# MCU.net
KiCad netlist of a schematic drawn in Altium Designer
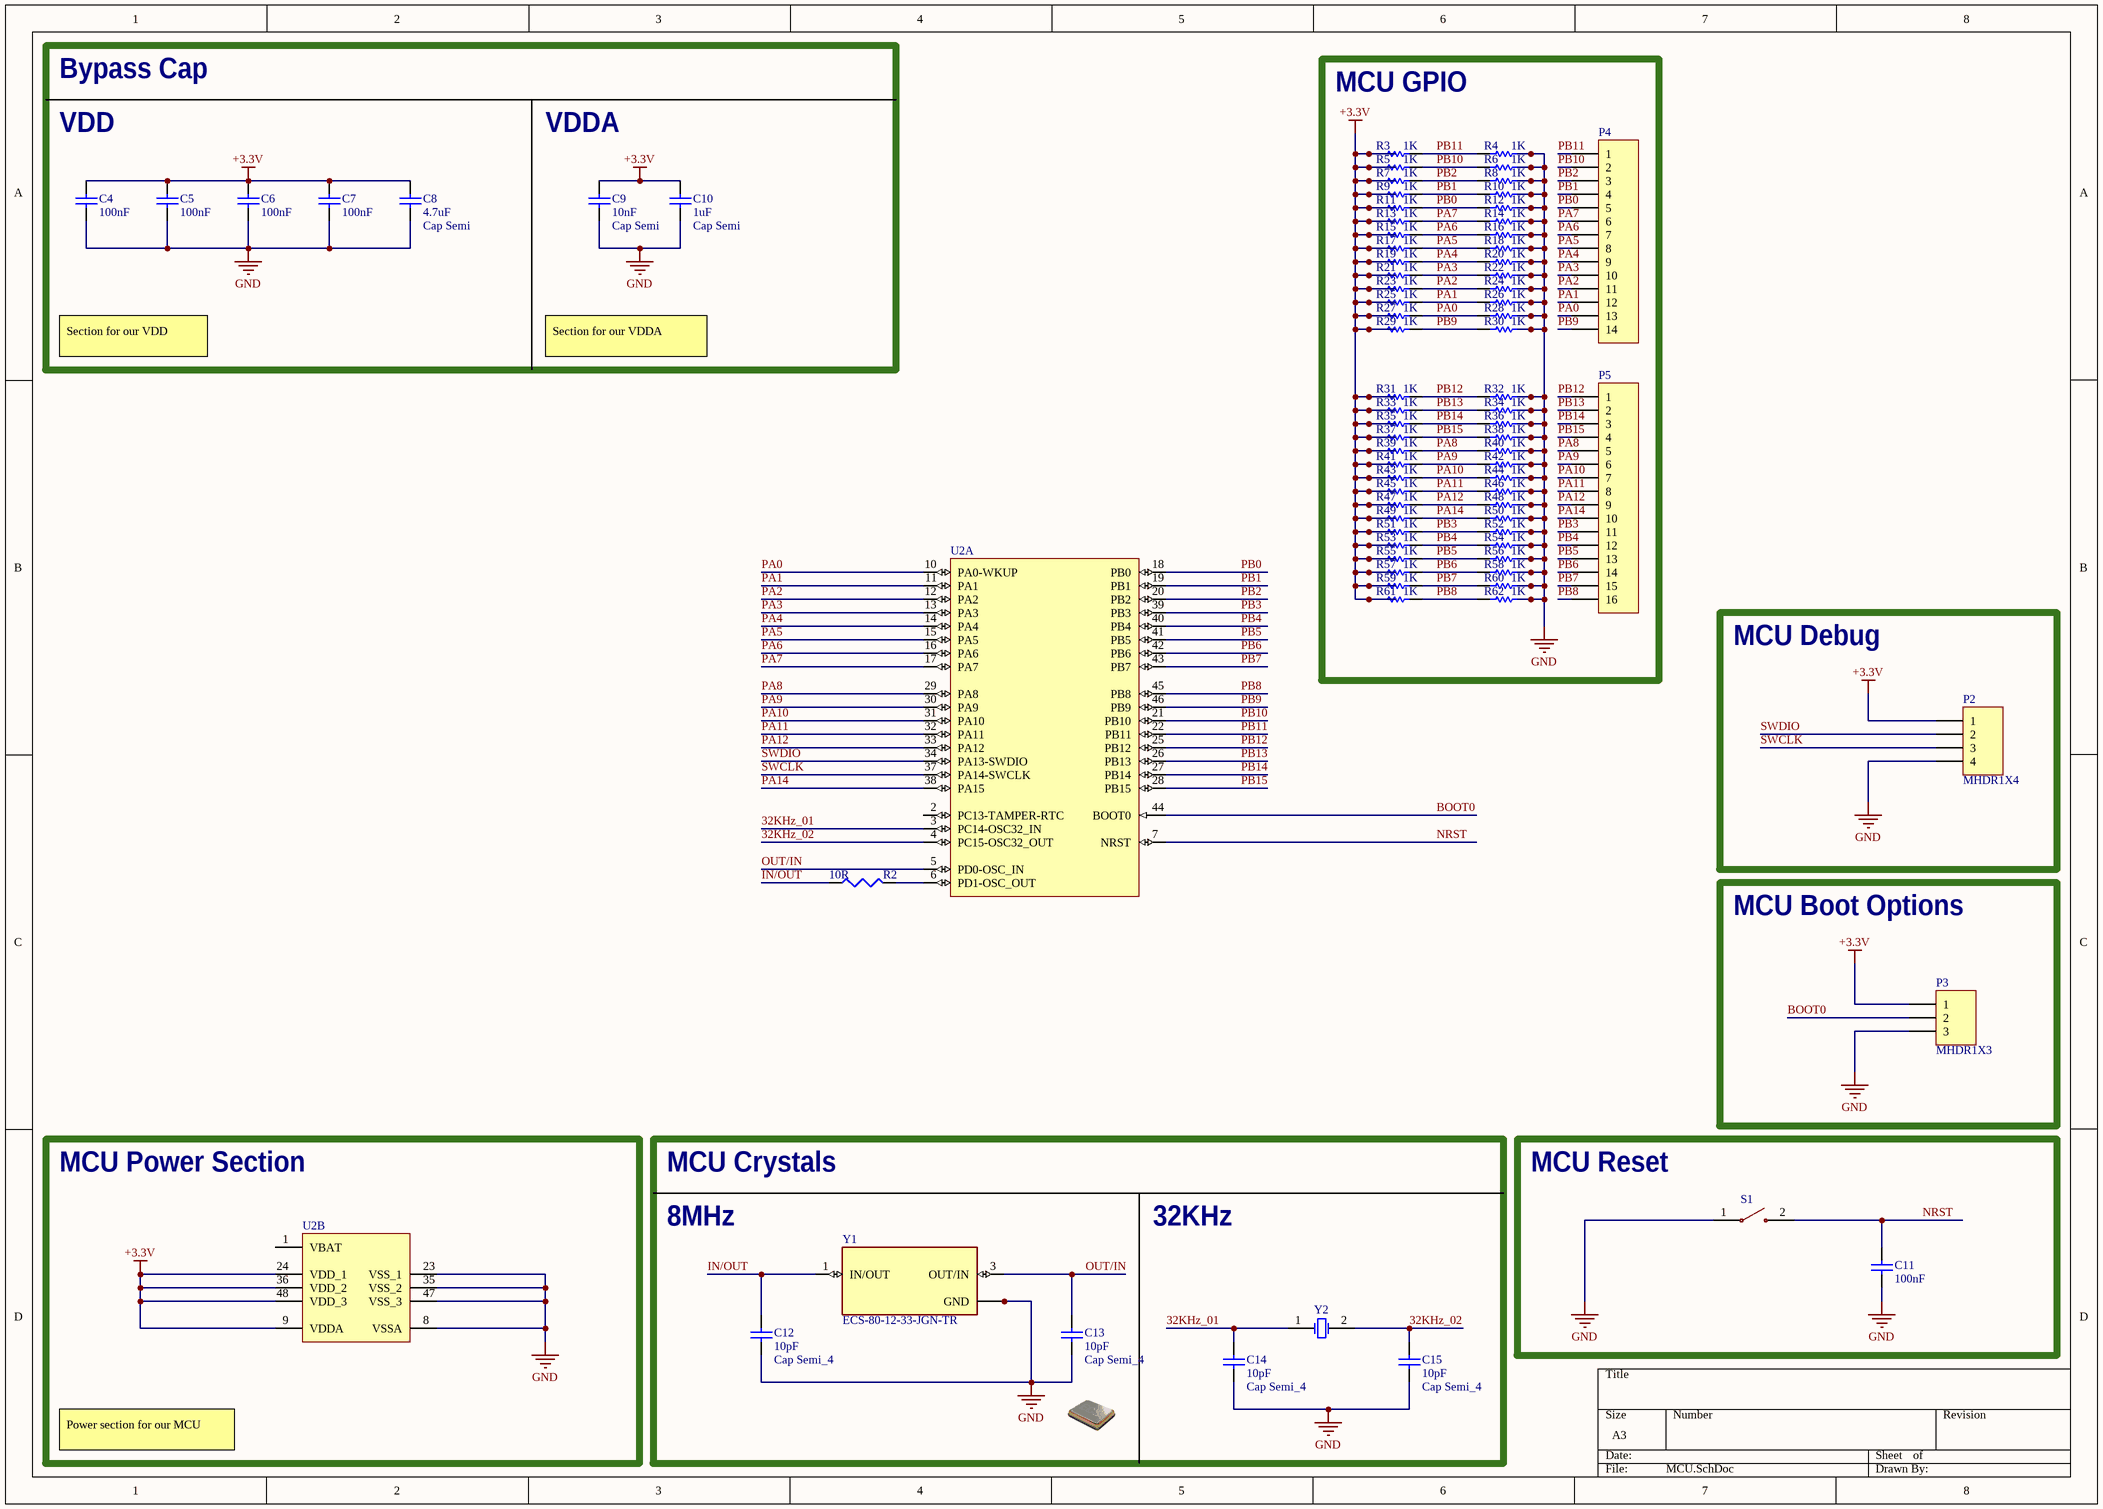
[diagram p0: MCU.SchDoc]

(export (version "E")
  (design (tool "Eeschema 10.0.6"))
  (components
    (comp (ref "C4")
      (value "100nF")
      (footprint "1608[0603]")
      (description "Capacitor (Semiconductor SIM Model)")
      (fields (field (name "PUBLISHER") "Altium Limited"))
      (libsource (lib "smartmcu") (part "Cap Semi"))
    )
    (comp (ref "C5")
      (value "100nF")
      (footprint "1608[0603]")
      (description "Capacitor (Semiconductor SIM Model)")
      (fields (field (name "PUBLISHER") "Altium Limited"))
      (libsource (lib "smartmcu") (part "Cap Semi"))
    )
    (comp (ref "C6")
      (value "100nF")
      (footprint "1608[0603]")
      (description "Capacitor (Semiconductor SIM Model)")
      (fields (field (name "PUBLISHER") "Altium Limited"))
      (libsource (lib "smartmcu") (part "Cap Semi"))
    )
    (comp (ref "C7")
      (value "100nF")
      (footprint "1608[0603]")
      (description "Capacitor (Semiconductor SIM Model)")
      (fields (field (name "PUBLISHER") "Altium Limited"))
      (libsource (lib "smartmcu") (part "Cap Semi"))
    )
    (comp (ref "C8")
      (value "Cap Semi")
      (footprint "1608[0603]")
      (description "Capacitor (Semiconductor SIM Model)")
      (fields (field (name "ALTIUM_VALUE") "4.7uF") (field (name "PUBLISHER") "Altium Limited"))
      (libsource (lib "smartmcu") (part "Cap Semi_1"))
    )
    (comp (ref "C9")
      (value "Cap Semi")
      (footprint "1608[0603]")
      (description "Capacitor (Semiconductor SIM Model)")
      (fields (field (name "ALTIUM_VALUE") "10nF") (field (name "PUBLISHER") "Altium Limited"))
      (libsource (lib "smartmcu") (part "Cap Semi_3"))
    )
    (comp (ref "C10")
      (value "Cap Semi")
      (footprint "1608[0603]")
      (description "Capacitor (Semiconductor SIM Model)")
      (fields (field (name "ALTIUM_VALUE") "1uF") (field (name "PUBLISHER") "Altium Limited"))
      (libsource (lib "smartmcu") (part "Cap Semi_2"))
    )
    (comp (ref "C11")
      (value "100nF")
      (footprint "1608[0603]")
      (description "Capacitor (Semiconductor SIM Model)")
      (fields (field (name "PUBLISHER") "Altium Limited"))
      (libsource (lib "smartmcu") (part "Cap Semi"))
    )
    (comp (ref "C12")
      (value "Cap Semi_4")
      (footprint "0402")
      (description "Capacitor (Semiconductor SIM Model)")
      (fields (field (name "ALTIUM_VALUE") "10pF") (field (name "PUBLISHER") "Altium Limited"))
      (libsource (lib "smartmcu") (part "Cap Semi_4"))
    )
    (comp (ref "C13")
      (value "Cap Semi_4")
      (footprint "0402")
      (description "Capacitor (Semiconductor SIM Model)")
      (fields (field (name "ALTIUM_VALUE") "10pF") (field (name "PUBLISHER") "Altium Limited"))
      (libsource (lib "smartmcu") (part "Cap Semi_4"))
    )
    (comp (ref "C14")
      (value "Cap Semi_4")
      (footprint "0402")
      (description "Capacitor (Semiconductor SIM Model)")
      (fields (field (name "ALTIUM_VALUE") "10pF") (field (name "PUBLISHER") "Altium Limited"))
      (libsource (lib "smartmcu") (part "Cap Semi_4"))
    )
    (comp (ref "C15")
      (value "Cap Semi_4")
      (footprint "0402")
      (description "Capacitor (Semiconductor SIM Model)")
      (fields (field (name "ALTIUM_VALUE") "10pF") (field (name "PUBLISHER") "Altium Limited"))
      (libsource (lib "smartmcu") (part "Cap Semi_4"))
    )
    (comp (ref "P2")
      (value "MHDR1X4")
      (footprint "MHDR1X4")
      (description "Header, 4-Pin")
      (fields (field (name "PUBLISHER") "Altium Limited"))
      (libsource (lib "Miscellaneous Connectors") (part "MHDR1X4"))
    )
    (comp (ref "P3")
      (value "MHDR1X3")
      (footprint "MHDR1X3")
      (description "Header, 3-Pin")
      (fields (field (name "PUBLISHER") "Altium Limited"))
      (libsource (lib "Miscellaneous Connectors") (part "MHDR1X3"))
    )
    (comp (ref "P4")
      (value "Header 14")
      (footprint "My_1X14")
      (description "Header, 14-Pin")
      (fields (field (name "ASID PART NUMBER") "Header 14-AS"))
      (libsource (lib "Mylib+Rev+4") (part "Header 14"))
    )
    (comp (ref "P5")
      (value "Header 16")
      (footprint "MY_FE16")
      (description "Header, 16-Pin")
      (fields (field (name "ASID PART NUMBER") "Header 16-AS"))
      (libsource (lib "Mylib+Rev+4") (part "Header 16"))
    )
    (comp (ref "R2")
      (value "10R")
      (footprint "J1-0603")
      (description "Resistor")
      (fields (field (name "PUBLISHER") "Altium Limited"))
      (libsource (lib "smartmcu") (part "Res3"))
    )
    (comp (ref "R3")
      (value "1K")
      (footprint "MY_0603")
      (description "Standard resistor")
      (fields (field (name "ASID PART NUMBER") "Res-AS"))
      (libsource (lib "Mylib+Rev+4") (part "Res"))
    )
    (comp (ref "R4")
      (value "1K")
      (footprint "MY_0603")
      (description "Standard resistor")
      (fields (field (name "ASID PART NUMBER") "Res-AS"))
      (libsource (lib "Mylib+Rev+4") (part "Res"))
    )
    (comp (ref "R5")
      (value "1K")
      (footprint "MY_0603")
      (description "Standard resistor")
      (fields (field (name "ASID PART NUMBER") "Res-AS"))
      (libsource (lib "Mylib+Rev+4") (part "Res"))
    )
    (comp (ref "R6")
      (value "1K")
      (footprint "MY_0603")
      (description "Standard resistor")
      (fields (field (name "ASID PART NUMBER") "Res-AS"))
      (libsource (lib "Mylib+Rev+4") (part "Res"))
    )
    (comp (ref "R7")
      (value "1K")
      (footprint "MY_0603")
      (description "Standard resistor")
      (fields (field (name "ASID PART NUMBER") "Res-AS"))
      (libsource (lib "Mylib+Rev+4") (part "Res"))
    )
    (comp (ref "R8")
      (value "1K")
      (footprint "MY_0603")
      (description "Standard resistor")
      (fields (field (name "ASID PART NUMBER") "Res-AS"))
      (libsource (lib "Mylib+Rev+4") (part "Res"))
    )
    (comp (ref "R9")
      (value "1K")
      (footprint "MY_0603")
      (description "Standard resistor")
      (fields (field (name "ASID PART NUMBER") "Res-AS"))
      (libsource (lib "Mylib+Rev+4") (part "Res"))
    )
    (comp (ref "R10")
      (value "1K")
      (footprint "MY_0603")
      (description "Standard resistor")
      (fields (field (name "ASID PART NUMBER") "Res-AS"))
      (libsource (lib "Mylib+Rev+4") (part "Res"))
    )
    (comp (ref "R11")
      (value "1K")
      (footprint "MY_0603")
      (description "Standard resistor")
      (fields (field (name "ASID PART NUMBER") "Res-AS"))
      (libsource (lib "Mylib+Rev+4") (part "Res"))
    )
    (comp (ref "R12")
      (value "1K")
      (footprint "MY_0603")
      (description "Standard resistor")
      (fields (field (name "ASID PART NUMBER") "Res-AS"))
      (libsource (lib "Mylib+Rev+4") (part "Res"))
    )
    (comp (ref "R13")
      (value "1K")
      (footprint "MY_0603")
      (description "Standard resistor")
      (fields (field (name "ASID PART NUMBER") "Res-AS"))
      (libsource (lib "Mylib+Rev+4") (part "Res"))
    )
    (comp (ref "R14")
      (value "1K")
      (footprint "MY_0603")
      (description "Standard resistor")
      (fields (field (name "ASID PART NUMBER") "Res-AS"))
      (libsource (lib "Mylib+Rev+4") (part "Res"))
    )
    (comp (ref "R15")
      (value "1K")
      (footprint "MY_0603")
      (description "Standard resistor")
      (fields (field (name "ASID PART NUMBER") "Res-AS"))
      (libsource (lib "Mylib+Rev+4") (part "Res"))
    )
    (comp (ref "R16")
      (value "1K")
      (footprint "MY_0603")
      (description "Standard resistor")
      (fields (field (name "ASID PART NUMBER") "Res-AS"))
      (libsource (lib "Mylib+Rev+4") (part "Res"))
    )
    (comp (ref "R17")
      (value "1K")
      (footprint "MY_0603")
      (description "Standard resistor")
      (fields (field (name "ASID PART NUMBER") "Res-AS"))
      (libsource (lib "Mylib+Rev+4") (part "Res"))
    )
    (comp (ref "R18")
      (value "1K")
      (footprint "MY_0603")
      (description "Standard resistor")
      (fields (field (name "ASID PART NUMBER") "Res-AS"))
      (libsource (lib "Mylib+Rev+4") (part "Res"))
    )
    (comp (ref "R19")
      (value "1K")
      (footprint "MY_0603")
      (description "Standard resistor")
      (fields (field (name "ASID PART NUMBER") "Res-AS"))
      (libsource (lib "Mylib+Rev+4") (part "Res"))
    )
    (comp (ref "R20")
      (value "1K")
      (footprint "MY_0603")
      (description "Standard resistor")
      (fields (field (name "ASID PART NUMBER") "Res-AS"))
      (libsource (lib "Mylib+Rev+4") (part "Res"))
    )
    (comp (ref "R21")
      (value "1K")
      (footprint "MY_0603")
      (description "Standard resistor")
      (fields (field (name "ASID PART NUMBER") "Res-AS"))
      (libsource (lib "Mylib+Rev+4") (part "Res"))
    )
    (comp (ref "R22")
      (value "1K")
      (footprint "MY_0603")
      (description "Standard resistor")
      (fields (field (name "ASID PART NUMBER") "Res-AS"))
      (libsource (lib "Mylib+Rev+4") (part "Res"))
    )
    (comp (ref "R23")
      (value "1K")
      (footprint "MY_0603")
      (description "Standard resistor")
      (fields (field (name "ASID PART NUMBER") "Res-AS"))
      (libsource (lib "Mylib+Rev+4") (part "Res"))
    )
    (comp (ref "R24")
      (value "1K")
      (footprint "MY_0603")
      (description "Standard resistor")
      (fields (field (name "ASID PART NUMBER") "Res-AS"))
      (libsource (lib "Mylib+Rev+4") (part "Res"))
    )
    (comp (ref "R25")
      (value "1K")
      (footprint "MY_0603")
      (description "Standard resistor")
      (fields (field (name "ASID PART NUMBER") "Res-AS"))
      (libsource (lib "Mylib+Rev+4") (part "Res"))
    )
    (comp (ref "R26")
      (value "1K")
      (footprint "MY_0603")
      (description "Standard resistor")
      (fields (field (name "ASID PART NUMBER") "Res-AS"))
      (libsource (lib "Mylib+Rev+4") (part "Res"))
    )
    (comp (ref "R27")
      (value "1K")
      (footprint "MY_0603")
      (description "Standard resistor")
      (fields (field (name "ASID PART NUMBER") "Res-AS"))
      (libsource (lib "Mylib+Rev+4") (part "Res"))
    )
    (comp (ref "R28")
      (value "1K")
      (footprint "MY_0603")
      (description "Standard resistor")
      (fields (field (name "ASID PART NUMBER") "Res-AS"))
      (libsource (lib "Mylib+Rev+4") (part "Res"))
    )
    (comp (ref "R29")
      (value "1K")
      (footprint "MY_0603")
      (description "Standard resistor")
      (fields (field (name "ASID PART NUMBER") "Res-AS"))
      (libsource (lib "Mylib+Rev+4") (part "Res"))
    )
    (comp (ref "R30")
      (value "1K")
      (footprint "MY_0603")
      (description "Standard resistor")
      (fields (field (name "ASID PART NUMBER") "Res-AS"))
      (libsource (lib "Mylib+Rev+4") (part "Res"))
    )
    (comp (ref "R31")
      (value "1K")
      (footprint "MY_0603")
      (description "Standard resistor")
      (fields (field (name "ASID PART NUMBER") "Res-AS"))
      (libsource (lib "Mylib+Rev+4") (part "Res"))
    )
    (comp (ref "R32")
      (value "1K")
      (footprint "MY_0603")
      (description "Standard resistor")
      (fields (field (name "ASID PART NUMBER") "Res-AS"))
      (libsource (lib "Mylib+Rev+4") (part "Res"))
    )
    (comp (ref "R33")
      (value "1K")
      (footprint "MY_0603")
      (description "Standard resistor")
      (fields (field (name "ASID PART NUMBER") "Res-AS"))
      (libsource (lib "Mylib+Rev+4") (part "Res"))
    )
    (comp (ref "R34")
      (value "1K")
      (footprint "MY_0603")
      (description "Standard resistor")
      (fields (field (name "ASID PART NUMBER") "Res-AS"))
      (libsource (lib "Mylib+Rev+4") (part "Res"))
    )
    (comp (ref "R35")
      (value "1K")
      (footprint "MY_0603")
      (description "Standard resistor")
      (fields (field (name "ASID PART NUMBER") "Res-AS"))
      (libsource (lib "Mylib+Rev+4") (part "Res"))
    )
    (comp (ref "R36")
      (value "1K")
      (footprint "MY_0603")
      (description "Standard resistor")
      (fields (field (name "ASID PART NUMBER") "Res-AS"))
      (libsource (lib "Mylib+Rev+4") (part "Res"))
    )
    (comp (ref "R37")
      (value "1K")
      (footprint "MY_0603")
      (description "Standard resistor")
      (fields (field (name "ASID PART NUMBER") "Res-AS"))
      (libsource (lib "Mylib+Rev+4") (part "Res"))
    )
    (comp (ref "R38")
      (value "1K")
      (footprint "MY_0603")
      (description "Standard resistor")
      (fields (field (name "ASID PART NUMBER") "Res-AS"))
      (libsource (lib "Mylib+Rev+4") (part "Res"))
    )
    (comp (ref "R39")
      (value "1K")
      (footprint "MY_0603")
      (description "Standard resistor")
      (fields (field (name "ASID PART NUMBER") "Res-AS"))
      (libsource (lib "Mylib+Rev+4") (part "Res"))
    )
    (comp (ref "R40")
      (value "1K")
      (footprint "MY_0603")
      (description "Standard resistor")
      (fields (field (name "ASID PART NUMBER") "Res-AS"))
      (libsource (lib "Mylib+Rev+4") (part "Res"))
    )
    (comp (ref "R41")
      (value "1K")
      (footprint "MY_0603")
      (description "Standard resistor")
      (fields (field (name "ASID PART NUMBER") "Res-AS"))
      (libsource (lib "Mylib+Rev+4") (part "Res"))
    )
    (comp (ref "R42")
      (value "1K")
      (footprint "MY_0603")
      (description "Standard resistor")
      (fields (field (name "ASID PART NUMBER") "Res-AS"))
      (libsource (lib "Mylib+Rev+4") (part "Res"))
    )
    (comp (ref "R43")
      (value "1K")
      (footprint "MY_0603")
      (description "Standard resistor")
      (fields (field (name "ASID PART NUMBER") "Res-AS"))
      (libsource (lib "Mylib+Rev+4") (part "Res"))
    )
    (comp (ref "R44")
      (value "1K")
      (footprint "MY_0603")
      (description "Standard resistor")
      (fields (field (name "ASID PART NUMBER") "Res-AS"))
      (libsource (lib "Mylib+Rev+4") (part "Res"))
    )
    (comp (ref "R45")
      (value "1K")
      (footprint "MY_0603")
      (description "Standard resistor")
      (fields (field (name "ASID PART NUMBER") "Res-AS"))
      (libsource (lib "Mylib+Rev+4") (part "Res"))
    )
    (comp (ref "R46")
      (value "1K")
      (footprint "MY_0603")
      (description "Standard resistor")
      (fields (field (name "ASID PART NUMBER") "Res-AS"))
      (libsource (lib "Mylib+Rev+4") (part "Res"))
    )
    (comp (ref "R47")
      (value "1K")
      (footprint "MY_0603")
      (description "Standard resistor")
      (fields (field (name "ASID PART NUMBER") "Res-AS"))
      (libsource (lib "Mylib+Rev+4") (part "Res"))
    )
    (comp (ref "R48")
      (value "1K")
      (footprint "MY_0603")
      (description "Standard resistor")
      (fields (field (name "ASID PART NUMBER") "Res-AS"))
      (libsource (lib "Mylib+Rev+4") (part "Res"))
    )
    (comp (ref "R49")
      (value "1K")
      (footprint "MY_0603")
      (description "Standard resistor")
      (fields (field (name "ASID PART NUMBER") "Res-AS"))
      (libsource (lib "Mylib+Rev+4") (part "Res"))
    )
    (comp (ref "R50")
      (value "1K")
      (footprint "MY_0603")
      (description "Standard resistor")
      (fields (field (name "ASID PART NUMBER") "Res-AS"))
      (libsource (lib "Mylib+Rev+4") (part "Res"))
    )
    (comp (ref "R51")
      (value "1K")
      (footprint "MY_0603")
      (description "Standard resistor")
      (fields (field (name "ASID PART NUMBER") "Res-AS"))
      (libsource (lib "Mylib+Rev+4") (part "Res"))
    )
    (comp (ref "R52")
      (value "1K")
      (footprint "MY_0603")
      (description "Standard resistor")
      (fields (field (name "ASID PART NUMBER") "Res-AS"))
      (libsource (lib "Mylib+Rev+4") (part "Res"))
    )
    (comp (ref "R53")
      (value "1K")
      (footprint "MY_0603")
      (description "Standard resistor")
      (fields (field (name "ASID PART NUMBER") "Res-AS"))
      (libsource (lib "Mylib+Rev+4") (part "Res"))
    )
    (comp (ref "R54")
      (value "1K")
      (footprint "MY_0603")
      (description "Standard resistor")
      (fields (field (name "ASID PART NUMBER") "Res-AS"))
      (libsource (lib "Mylib+Rev+4") (part "Res"))
    )
    (comp (ref "R55")
      (value "1K")
      (footprint "MY_0603")
      (description "Standard resistor")
      (fields (field (name "ASID PART NUMBER") "Res-AS"))
      (libsource (lib "Mylib+Rev+4") (part "Res"))
    )
    (comp (ref "R56")
      (value "1K")
      (footprint "MY_0603")
      (description "Standard resistor")
      (fields (field (name "ASID PART NUMBER") "Res-AS"))
      (libsource (lib "Mylib+Rev+4") (part "Res"))
    )
    (comp (ref "R57")
      (value "1K")
      (footprint "MY_0603")
      (description "Standard resistor")
      (fields (field (name "ASID PART NUMBER") "Res-AS"))
      (libsource (lib "Mylib+Rev+4") (part "Res"))
    )
    (comp (ref "R58")
      (value "1K")
      (footprint "MY_0603")
      (description "Standard resistor")
      (fields (field (name "ASID PART NUMBER") "Res-AS"))
      (libsource (lib "Mylib+Rev+4") (part "Res"))
    )
    (comp (ref "R59")
      (value "1K")
      (footprint "MY_0603")
      (description "Standard resistor")
      (fields (field (name "ASID PART NUMBER") "Res-AS"))
      (libsource (lib "Mylib+Rev+4") (part "Res"))
    )
    (comp (ref "R60")
      (value "1K")
      (footprint "MY_0603")
      (description "Standard resistor")
      (fields (field (name "ASID PART NUMBER") "Res-AS"))
      (libsource (lib "Mylib+Rev+4") (part "Res"))
    )
    (comp (ref "R61")
      (value "1K")
      (footprint "MY_0603")
      (description "Standard resistor")
      (fields (field (name "ASID PART NUMBER") "Res-AS"))
      (libsource (lib "Mylib+Rev+4") (part "Res"))
    )
    (comp (ref "R62")
      (value "1K")
      (footprint "MY_0603")
      (description "Standard resistor")
      (fields (field (name "ASID PART NUMBER") "Res-AS"))
      (libsource (lib "Mylib+Rev+4") (part "Res"))
    )
    (comp (ref "S1")
      (value "PUSH_BUTTON_SMD_3X4X2")
      (footprint "PUSH_BUTTON_SMD_3X4X2")
      (description "Push Button Tactile Switch SMD 2 Pins 3x4x2mm.")
      (libsource (lib "Buttons & Switches") (part "PUSH_BUTTON_SMD_3X4X2"))
    )
    (comp (ref "U2")
      (value "~")
      (footprint "STM-LQFP48_N")
      (fields (field (name "PARTNUMBER") "STM32F103C8T6"))
      (libsource (lib "smartmcu") (part "STM32F103C8T6"))
    )
    (comp (ref "Y1")
      (value "ECS-80-12-33-JGN-TR")
      (footprint "XTAL_ECS-240-8-33-AGN-TR")
      (description "8 MHz Â±20ppm Crystal 12pF 400 Ohms 4-SMD, No Lead")
      (fields (field (name "MF") "ECS Inc."))
      (libsource (lib "ECS-80-12-33-JGN-TR") (part "ECS-80-12-33-JGN-TR"))
    )
    (comp (ref "Y2")
      (value "~")
      (footprint "R38")
      (description "Crystal Oscillator")
      (fields (field (name "PUBLISHER") "Altium Limited"))
      (libsource (lib "smartmcu") (part "XTAL"))
    )
  )
  (nets
    (net (code "1") (name "+3.3V") (class "Default")
      (node (ref "C10") (pin "2") (pinfunction "2_2") (pintype "passive"))
      (node (ref "C4") (pin "2") (pinfunction "2_2") (pintype "passive"))
      (node (ref "C5") (pin "2") (pinfunction "2_2") (pintype "passive"))
      (node (ref "C6") (pin "2") (pinfunction "2_2") (pintype "passive"))
      (node (ref "C7") (pin "2") (pinfunction "2_2") (pintype "passive"))
      (node (ref "C8") (pin "2") (pinfunction "2_2") (pintype "passive"))
      (node (ref "C9") (pin "2") (pinfunction "2_2") (pintype "passive"))
      (node (ref "P2") (pin "1") (pinfunction "1_1") (pintype "passive"))
      (node (ref "P3") (pin "1") (pinfunction "1_1") (pintype "passive"))
      (node (ref "R11") (pin "1") (pinfunction "1_1") (pintype "passive"))
      (node (ref "R13") (pin "1") (pinfunction "1_1") (pintype "passive"))
      (node (ref "R15") (pin "1") (pinfunction "1_1") (pintype "passive"))
      (node (ref "R17") (pin "1") (pinfunction "1_1") (pintype "passive"))
      (node (ref "R19") (pin "1") (pinfunction "1_1") (pintype "passive"))
      (node (ref "R21") (pin "1") (pinfunction "1_1") (pintype "passive"))
      (node (ref "R23") (pin "1") (pinfunction "1_1") (pintype "passive"))
      (node (ref "R25") (pin "1") (pinfunction "1_1") (pintype "passive"))
      (node (ref "R27") (pin "1") (pinfunction "1_1") (pintype "passive"))
      (node (ref "R29") (pin "1") (pinfunction "1_1") (pintype "passive"))
      (node (ref "R3") (pin "1") (pinfunction "1_1") (pintype "passive"))
      (node (ref "R31") (pin "1") (pinfunction "1_1") (pintype "passive"))
      (node (ref "R33") (pin "1") (pinfunction "1_1") (pintype "passive"))
      (node (ref "R35") (pin "1") (pinfunction "1_1") (pintype "passive"))
      (node (ref "R37") (pin "1") (pinfunction "1_1") (pintype "passive"))
      (node (ref "R39") (pin "1") (pinfunction "1_1") (pintype "passive"))
      (node (ref "R41") (pin "1") (pinfunction "1_1") (pintype "passive"))
      (node (ref "R43") (pin "1") (pinfunction "1_1") (pintype "passive"))
      (node (ref "R45") (pin "1") (pinfunction "1_1") (pintype "passive"))
      (node (ref "R47") (pin "1") (pinfunction "1_1") (pintype "passive"))
      (node (ref "R49") (pin "1") (pinfunction "1_1") (pintype "passive"))
      (node (ref "R5") (pin "1") (pinfunction "1_1") (pintype "passive"))
      (node (ref "R51") (pin "1") (pinfunction "1_1") (pintype "passive"))
      (node (ref "R53") (pin "1") (pinfunction "1_1") (pintype "passive"))
      (node (ref "R55") (pin "1") (pinfunction "1_1") (pintype "passive"))
      (node (ref "R57") (pin "1") (pinfunction "1_1") (pintype "passive"))
      (node (ref "R59") (pin "1") (pinfunction "1_1") (pintype "passive"))
      (node (ref "R61") (pin "1") (pinfunction "1_1") (pintype "passive"))
      (node (ref "R7") (pin "1") (pinfunction "1_1") (pintype "passive"))
      (node (ref "R9") (pin "1") (pinfunction "1_1") (pintype "passive"))
      (node (ref "U2") (pin "24") (pinfunction "VDD_1_24") (pintype "power_in"))
      (node (ref "U2") (pin "36") (pinfunction "VDD_2_36") (pintype "power_in"))
      (node (ref "U2") (pin "48") (pinfunction "VDD_3_48") (pintype "power_in"))
      (node (ref "U2") (pin "9") (pinfunction "VDDA_9") (pintype "power_in"))
    )
    (net (code "2") (name "/32KHz_01") (class "Default")
      (node (ref "C14") (pin "1") (pinfunction "1_1") (pintype "passive"))
      (node (ref "U2") (pin "3") (pinfunction "PC14-OSC32_IN_3") (pintype "bidirectional"))
      (node (ref "Y2") (pin "1") (pinfunction "OSC1_1") (pintype "passive"))
    )
    (net (code "3") (name "/32KHz_02") (class "Default")
      (node (ref "C15") (pin "1") (pinfunction "1_1") (pintype "passive"))
      (node (ref "U2") (pin "4") (pinfunction "PC15-OSC32_OUT_4") (pintype "bidirectional"))
      (node (ref "Y2") (pin "2") (pinfunction "OSC2_2") (pintype "passive"))
    )
    (net (code "4") (name "/BOOT0") (class "Default")
      (node (ref "P3") (pin "2") (pinfunction "2_2") (pintype "passive"))
      (node (ref "U2") (pin "44") (pinfunction "BOOT0_44") (pintype "input"))
    )
    (net (code "5") (name "/IN{slash}OUT") (class "Default")
      (node (ref "C12") (pin "1") (pinfunction "1_1") (pintype "passive"))
      (node (ref "R2") (pin "1") (pinfunction "1_1") (pintype "passive"))
      (node (ref "Y1") (pin "1") (pinfunction "IN/OUT_1") (pintype "bidirectional"))
    )
    (net (code "6") (name "/NRST") (class "Default")
      (node (ref "C11") (pin "2") (pinfunction "2_2") (pintype "passive"))
      (node (ref "S1") (pin "2") (pinfunction "2_2") (pintype "passive"))
      (node (ref "U2") (pin "7") (pinfunction "NRST_7") (pintype "bidirectional"))
    )
    (net (code "7") (name "/OUT{slash}IN") (class "Default")
      (node (ref "C13") (pin "1") (pinfunction "1_1") (pintype "passive"))
      (node (ref "U2") (pin "5") (pinfunction "PD0-OSC_IN_5") (pintype "bidirectional"))
      (node (ref "Y1") (pin "3") (pinfunction "OUT/IN_3") (pintype "bidirectional"))
    )
    (net (code "8") (name "/PA0") (class "Default")
      (node (ref "P4") (pin "13") (pinfunction "13_13") (pintype "passive"))
      (node (ref "R27") (pin "2") (pinfunction "2_2") (pintype "passive"))
      (node (ref "R28") (pin "1") (pinfunction "1_1") (pintype "passive"))
      (node (ref "U2") (pin "10") (pinfunction "PA0-WKUP_10") (pintype "bidirectional"))
    )
    (net (code "9") (name "/PA1") (class "Default")
      (node (ref "P4") (pin "12") (pinfunction "12_12") (pintype "passive"))
      (node (ref "R25") (pin "2") (pinfunction "2_2") (pintype "passive"))
      (node (ref "R26") (pin "1") (pinfunction "1_1") (pintype "passive"))
      (node (ref "U2") (pin "11") (pinfunction "PA1_11") (pintype "bidirectional"))
    )
    (net (code "10") (name "/PA2") (class "Default")
      (node (ref "P4") (pin "11") (pinfunction "11_11") (pintype "passive"))
      (node (ref "R23") (pin "2") (pinfunction "2_2") (pintype "passive"))
      (node (ref "R24") (pin "1") (pinfunction "1_1") (pintype "passive"))
      (node (ref "U2") (pin "12") (pinfunction "PA2_12") (pintype "bidirectional"))
    )
    (net (code "11") (name "/PA3") (class "Default")
      (node (ref "P4") (pin "10") (pinfunction "10_10") (pintype "passive"))
      (node (ref "R21") (pin "2") (pinfunction "2_2") (pintype "passive"))
      (node (ref "R22") (pin "1") (pinfunction "1_1") (pintype "passive"))
      (node (ref "U2") (pin "13") (pinfunction "PA3_13") (pintype "bidirectional"))
    )
    (net (code "12") (name "/PA4") (class "Default")
      (node (ref "P4") (pin "9") (pinfunction "9_9") (pintype "passive"))
      (node (ref "R19") (pin "2") (pinfunction "2_2") (pintype "passive"))
      (node (ref "R20") (pin "1") (pinfunction "1_1") (pintype "passive"))
      (node (ref "U2") (pin "14") (pinfunction "PA4_14") (pintype "bidirectional"))
    )
    (net (code "13") (name "/PA5") (class "Default")
      (node (ref "P4") (pin "8") (pinfunction "8_8") (pintype "passive"))
      (node (ref "R17") (pin "2") (pinfunction "2_2") (pintype "passive"))
      (node (ref "R18") (pin "1") (pinfunction "1_1") (pintype "passive"))
      (node (ref "U2") (pin "15") (pinfunction "PA5_15") (pintype "bidirectional"))
    )
    (net (code "14") (name "/PA6") (class "Default")
      (node (ref "P4") (pin "7") (pinfunction "7_7") (pintype "passive"))
      (node (ref "R15") (pin "2") (pinfunction "2_2") (pintype "passive"))
      (node (ref "R16") (pin "1") (pinfunction "1_1") (pintype "passive"))
      (node (ref "U2") (pin "16") (pinfunction "PA6_16") (pintype "bidirectional"))
    )
    (net (code "15") (name "/PA7") (class "Default")
      (node (ref "P4") (pin "6") (pinfunction "6_6") (pintype "passive"))
      (node (ref "R13") (pin "2") (pinfunction "2_2") (pintype "passive"))
      (node (ref "R14") (pin "1") (pinfunction "1_1") (pintype "passive"))
      (node (ref "U2") (pin "17") (pinfunction "PA7_17") (pintype "bidirectional"))
    )
    (net (code "16") (name "/PA8") (class "Default")
      (node (ref "P5") (pin "5") (pinfunction "5_5") (pintype "passive"))
      (node (ref "R39") (pin "2") (pinfunction "2_2") (pintype "passive"))
      (node (ref "R40") (pin "1") (pinfunction "1_1") (pintype "passive"))
      (node (ref "U2") (pin "29") (pinfunction "PA8_29") (pintype "bidirectional"))
    )
    (net (code "17") (name "/PA9") (class "Default")
      (node (ref "P5") (pin "6") (pinfunction "6_6") (pintype "passive"))
      (node (ref "R41") (pin "2") (pinfunction "2_2") (pintype "passive"))
      (node (ref "R42") (pin "1") (pinfunction "1_1") (pintype "passive"))
      (node (ref "U2") (pin "30") (pinfunction "PA9_30") (pintype "bidirectional"))
    )
    (net (code "18") (name "/PA10") (class "Default")
      (node (ref "P5") (pin "7") (pinfunction "7_7") (pintype "passive"))
      (node (ref "R43") (pin "2") (pinfunction "2_2") (pintype "passive"))
      (node (ref "R44") (pin "1") (pinfunction "1_1") (pintype "passive"))
      (node (ref "U2") (pin "31") (pinfunction "PA10_31") (pintype "bidirectional"))
    )
    (net (code "19") (name "/PA11") (class "Default")
      (node (ref "P5") (pin "8") (pinfunction "8_8") (pintype "passive"))
      (node (ref "R45") (pin "2") (pinfunction "2_2") (pintype "passive"))
      (node (ref "R46") (pin "1") (pinfunction "1_1") (pintype "passive"))
      (node (ref "U2") (pin "32") (pinfunction "PA11_32") (pintype "bidirectional"))
    )
    (net (code "20") (name "/PA12") (class "Default")
      (node (ref "P5") (pin "9") (pinfunction "9_9") (pintype "passive"))
      (node (ref "R47") (pin "2") (pinfunction "2_2") (pintype "passive"))
      (node (ref "R48") (pin "1") (pinfunction "1_1") (pintype "passive"))
      (node (ref "U2") (pin "33") (pinfunction "PA12_33") (pintype "bidirectional"))
    )
    (net (code "21") (name "/PA14") (class "Default")
      (node (ref "P5") (pin "10") (pinfunction "10_10") (pintype "passive"))
      (node (ref "R49") (pin "2") (pinfunction "2_2") (pintype "passive"))
      (node (ref "R50") (pin "1") (pinfunction "1_1") (pintype "passive"))
      (node (ref "U2") (pin "38") (pinfunction "PA15_38") (pintype "bidirectional"))
    )
    (net (code "22") (name "/PB0") (class "Default")
      (node (ref "P4") (pin "5") (pinfunction "5_5") (pintype "passive"))
      (node (ref "R11") (pin "2") (pinfunction "2_2") (pintype "passive"))
      (node (ref "R12") (pin "1") (pinfunction "1_1") (pintype "passive"))
      (node (ref "U2") (pin "18") (pinfunction "PB0_18") (pintype "bidirectional"))
    )
    (net (code "23") (name "/PB1") (class "Default")
      (node (ref "P4") (pin "4") (pinfunction "4_4") (pintype "passive"))
      (node (ref "R10") (pin "1") (pinfunction "1_1") (pintype "passive"))
      (node (ref "R9") (pin "2") (pinfunction "2_2") (pintype "passive"))
      (node (ref "U2") (pin "19") (pinfunction "PB1_19") (pintype "bidirectional"))
    )
    (net (code "24") (name "/PB2") (class "Default")
      (node (ref "P4") (pin "3") (pinfunction "3_3") (pintype "passive"))
      (node (ref "R7") (pin "2") (pinfunction "2_2") (pintype "passive"))
      (node (ref "R8") (pin "1") (pinfunction "1_1") (pintype "passive"))
      (node (ref "U2") (pin "20") (pinfunction "PB2_20") (pintype "bidirectional"))
    )
    (net (code "25") (name "/PB3") (class "Default")
      (node (ref "P5") (pin "11") (pinfunction "11_11") (pintype "passive"))
      (node (ref "R51") (pin "2") (pinfunction "2_2") (pintype "passive"))
      (node (ref "R52") (pin "1") (pinfunction "1_1") (pintype "passive"))
      (node (ref "U2") (pin "39") (pinfunction "PB3_39") (pintype "bidirectional"))
    )
    (net (code "26") (name "/PB4") (class "Default")
      (node (ref "P5") (pin "12") (pinfunction "12_12") (pintype "passive"))
      (node (ref "R53") (pin "2") (pinfunction "2_2") (pintype "passive"))
      (node (ref "R54") (pin "1") (pinfunction "1_1") (pintype "passive"))
      (node (ref "U2") (pin "40") (pinfunction "PB4_40") (pintype "bidirectional"))
    )
    (net (code "27") (name "/PB5") (class "Default")
      (node (ref "P5") (pin "13") (pinfunction "13_13") (pintype "passive"))
      (node (ref "R55") (pin "2") (pinfunction "2_2") (pintype "passive"))
      (node (ref "R56") (pin "1") (pinfunction "1_1") (pintype "passive"))
      (node (ref "U2") (pin "41") (pinfunction "PB5_41") (pintype "bidirectional"))
    )
    (net (code "28") (name "/PB6") (class "Default")
      (node (ref "P5") (pin "14") (pinfunction "14_14") (pintype "passive"))
      (node (ref "R57") (pin "2") (pinfunction "2_2") (pintype "passive"))
      (node (ref "R58") (pin "1") (pinfunction "1_1") (pintype "passive"))
      (node (ref "U2") (pin "42") (pinfunction "PB6_42") (pintype "bidirectional"))
    )
    (net (code "29") (name "/PB7") (class "Default")
      (node (ref "P5") (pin "15") (pinfunction "15_15") (pintype "passive"))
      (node (ref "R59") (pin "2") (pinfunction "2_2") (pintype "passive"))
      (node (ref "R60") (pin "1") (pinfunction "1_1") (pintype "passive"))
      (node (ref "U2") (pin "43") (pinfunction "PB7_43") (pintype "bidirectional"))
    )
    (net (code "30") (name "/PB8") (class "Default")
      (node (ref "P5") (pin "16") (pinfunction "16_16") (pintype "passive"))
      (node (ref "R61") (pin "2") (pinfunction "2_2") (pintype "passive"))
      (node (ref "R62") (pin "1") (pinfunction "1_1") (pintype "passive"))
      (node (ref "U2") (pin "45") (pinfunction "PB8_45") (pintype "bidirectional"))
    )
    (net (code "31") (name "/PB9") (class "Default")
      (node (ref "P4") (pin "14") (pinfunction "14_14") (pintype "passive"))
      (node (ref "R29") (pin "2") (pinfunction "2_2") (pintype "passive"))
      (node (ref "R30") (pin "1") (pinfunction "1_1") (pintype "passive"))
      (node (ref "U2") (pin "46") (pinfunction "PB9_46") (pintype "bidirectional"))
    )
    (net (code "32") (name "/PB10") (class "Default")
      (node (ref "P4") (pin "2") (pinfunction "2_2") (pintype "passive"))
      (node (ref "R5") (pin "2") (pinfunction "2_2") (pintype "passive"))
      (node (ref "R6") (pin "1") (pinfunction "1_1") (pintype "passive"))
      (node (ref "U2") (pin "21") (pinfunction "PB10_21") (pintype "bidirectional"))
    )
    (net (code "33") (name "/PB11") (class "Default")
      (node (ref "P4") (pin "1") (pinfunction "1_1") (pintype "passive"))
      (node (ref "R3") (pin "2") (pinfunction "2_2") (pintype "passive"))
      (node (ref "R4") (pin "1") (pinfunction "1_1") (pintype "passive"))
      (node (ref "U2") (pin "22") (pinfunction "PB11_22") (pintype "bidirectional"))
    )
    (net (code "34") (name "/PB12") (class "Default")
      (node (ref "P5") (pin "1") (pinfunction "1_1") (pintype "passive"))
      (node (ref "R31") (pin "2") (pinfunction "2_2") (pintype "passive"))
      (node (ref "R32") (pin "1") (pinfunction "1_1") (pintype "passive"))
      (node (ref "U2") (pin "25") (pinfunction "PB12_25") (pintype "bidirectional"))
    )
    (net (code "35") (name "/PB13") (class "Default")
      (node (ref "P5") (pin "2") (pinfunction "2_2") (pintype "passive"))
      (node (ref "R33") (pin "2") (pinfunction "2_2") (pintype "passive"))
      (node (ref "R34") (pin "1") (pinfunction "1_1") (pintype "passive"))
      (node (ref "U2") (pin "26") (pinfunction "PB13_26") (pintype "bidirectional"))
    )
    (net (code "36") (name "/PB14") (class "Default")
      (node (ref "P5") (pin "3") (pinfunction "3_3") (pintype "passive"))
      (node (ref "R35") (pin "2") (pinfunction "2_2") (pintype "passive"))
      (node (ref "R36") (pin "1") (pinfunction "1_1") (pintype "passive"))
      (node (ref "U2") (pin "27") (pinfunction "PB14_27") (pintype "bidirectional"))
    )
    (net (code "37") (name "/PB15") (class "Default")
      (node (ref "P5") (pin "4") (pinfunction "4_4") (pintype "passive"))
      (node (ref "R37") (pin "2") (pinfunction "2_2") (pintype "passive"))
      (node (ref "R38") (pin "1") (pinfunction "1_1") (pintype "passive"))
      (node (ref "U2") (pin "28") (pinfunction "PB15_28") (pintype "bidirectional"))
    )
    (net (code "38") (name "/SWCLK") (class "Default")
      (node (ref "P2") (pin "3") (pinfunction "3_3") (pintype "passive"))
      (node (ref "U2") (pin "37") (pinfunction "PA14-SWCLK_37") (pintype "bidirectional"))
    )
    (net (code "39") (name "/SWDIO") (class "Default")
      (node (ref "P2") (pin "2") (pinfunction "2_2") (pintype "passive"))
      (node (ref "U2") (pin "34") (pinfunction "PA13-SWDIO_34") (pintype "bidirectional"))
    )
    (net (code "40") (name "GND") (class "Default")
      (node (ref "C10") (pin "1") (pinfunction "1_1") (pintype "passive"))
      (node (ref "C11") (pin "1") (pinfunction "1_1") (pintype "passive"))
      (node (ref "C12") (pin "2") (pinfunction "2_2") (pintype "passive"))
      (node (ref "C13") (pin "2") (pinfunction "2_2") (pintype "passive"))
      (node (ref "C14") (pin "2") (pinfunction "2_2") (pintype "passive"))
      (node (ref "C15") (pin "2") (pinfunction "2_2") (pintype "passive"))
      (node (ref "C4") (pin "1") (pinfunction "1_1") (pintype "passive"))
      (node (ref "C5") (pin "1") (pinfunction "1_1") (pintype "passive"))
      (node (ref "C6") (pin "1") (pinfunction "1_1") (pintype "passive"))
      (node (ref "C7") (pin "1") (pinfunction "1_1") (pintype "passive"))
      (node (ref "C8") (pin "1") (pinfunction "1_1") (pintype "passive"))
      (node (ref "C9") (pin "1") (pinfunction "1_1") (pintype "passive"))
      (node (ref "P2") (pin "4") (pinfunction "4_4") (pintype "passive"))
      (node (ref "P3") (pin "3") (pinfunction "3_3") (pintype "passive"))
      (node (ref "R10") (pin "2") (pinfunction "2_2") (pintype "passive"))
      (node (ref "R12") (pin "2") (pinfunction "2_2") (pintype "passive"))
      (node (ref "R14") (pin "2") (pinfunction "2_2") (pintype "passive"))
      (node (ref "R16") (pin "2") (pinfunction "2_2") (pintype "passive"))
      (node (ref "R18") (pin "2") (pinfunction "2_2") (pintype "passive"))
      (node (ref "R20") (pin "2") (pinfunction "2_2") (pintype "passive"))
      (node (ref "R22") (pin "2") (pinfunction "2_2") (pintype "passive"))
      (node (ref "R24") (pin "2") (pinfunction "2_2") (pintype "passive"))
      (node (ref "R26") (pin "2") (pinfunction "2_2") (pintype "passive"))
      (node (ref "R28") (pin "2") (pinfunction "2_2") (pintype "passive"))
      (node (ref "R30") (pin "2") (pinfunction "2_2") (pintype "passive"))
      (node (ref "R32") (pin "2") (pinfunction "2_2") (pintype "passive"))
      (node (ref "R34") (pin "2") (pinfunction "2_2") (pintype "passive"))
      (node (ref "R36") (pin "2") (pinfunction "2_2") (pintype "passive"))
      (node (ref "R38") (pin "2") (pinfunction "2_2") (pintype "passive"))
      (node (ref "R4") (pin "2") (pinfunction "2_2") (pintype "passive"))
      (node (ref "R40") (pin "2") (pinfunction "2_2") (pintype "passive"))
      (node (ref "R42") (pin "2") (pinfunction "2_2") (pintype "passive"))
      (node (ref "R44") (pin "2") (pinfunction "2_2") (pintype "passive"))
      (node (ref "R46") (pin "2") (pinfunction "2_2") (pintype "passive"))
      (node (ref "R48") (pin "2") (pinfunction "2_2") (pintype "passive"))
      (node (ref "R50") (pin "2") (pinfunction "2_2") (pintype "passive"))
      (node (ref "R52") (pin "2") (pinfunction "2_2") (pintype "passive"))
      (node (ref "R54") (pin "2") (pinfunction "2_2") (pintype "passive"))
      (node (ref "R56") (pin "2") (pinfunction "2_2") (pintype "passive"))
      (node (ref "R58") (pin "2") (pinfunction "2_2") (pintype "passive"))
      (node (ref "R6") (pin "2") (pinfunction "2_2") (pintype "passive"))
      (node (ref "R60") (pin "2") (pinfunction "2_2") (pintype "passive"))
      (node (ref "R62") (pin "2") (pinfunction "2_2") (pintype "passive"))
      (node (ref "R8") (pin "2") (pinfunction "2_2") (pintype "passive"))
      (node (ref "S1") (pin "1") (pinfunction "1_1") (pintype "passive"))
      (node (ref "U2") (pin "23") (pinfunction "VSS_1_23") (pintype "power_in"))
      (node (ref "U2") (pin "35") (pinfunction "VSS_2_35") (pintype "power_in"))
      (node (ref "U2") (pin "47") (pinfunction "VSS_3_47") (pintype "power_in"))
      (node (ref "U2") (pin "8") (pinfunction "VSSA_8") (pintype "power_in"))
      (node (ref "Y1") (pin "2") (pinfunction "GND_2") (pintype "power_in"))
      (node (ref "Y1") (pin "4") (pinfunction "GND_4") (pintype "power_in"))
    )
    (net (code "41") (name "Net-(U2A-PD1-OSC_OUT)") (class "Default")
      (node (ref "R2") (pin "2") (pinfunction "2_2") (pintype "passive"))
      (node (ref "U2") (pin "6") (pinfunction "PD1-OSC_OUT_6") (pintype "bidirectional"))
    )
    (net (code "42") (name "unconnected-(U2A-PC13-TAMPER-RTC-Pad2)") (class "Default")
      (node (ref "U2") (pin "2") (pinfunction "PC13-TAMPER-RTC_2") (pintype "bidirectional"))
    )
    (net (code "43") (name "unconnected-(U2B-VBAT-Pad1)") (class "Default")
      (node (ref "U2") (pin "1") (pinfunction "VBAT_1") (pintype "power_in"))
    )
  )
)
